# fpga.net
KiCad netlist of a schematic drawn in Altium Designer
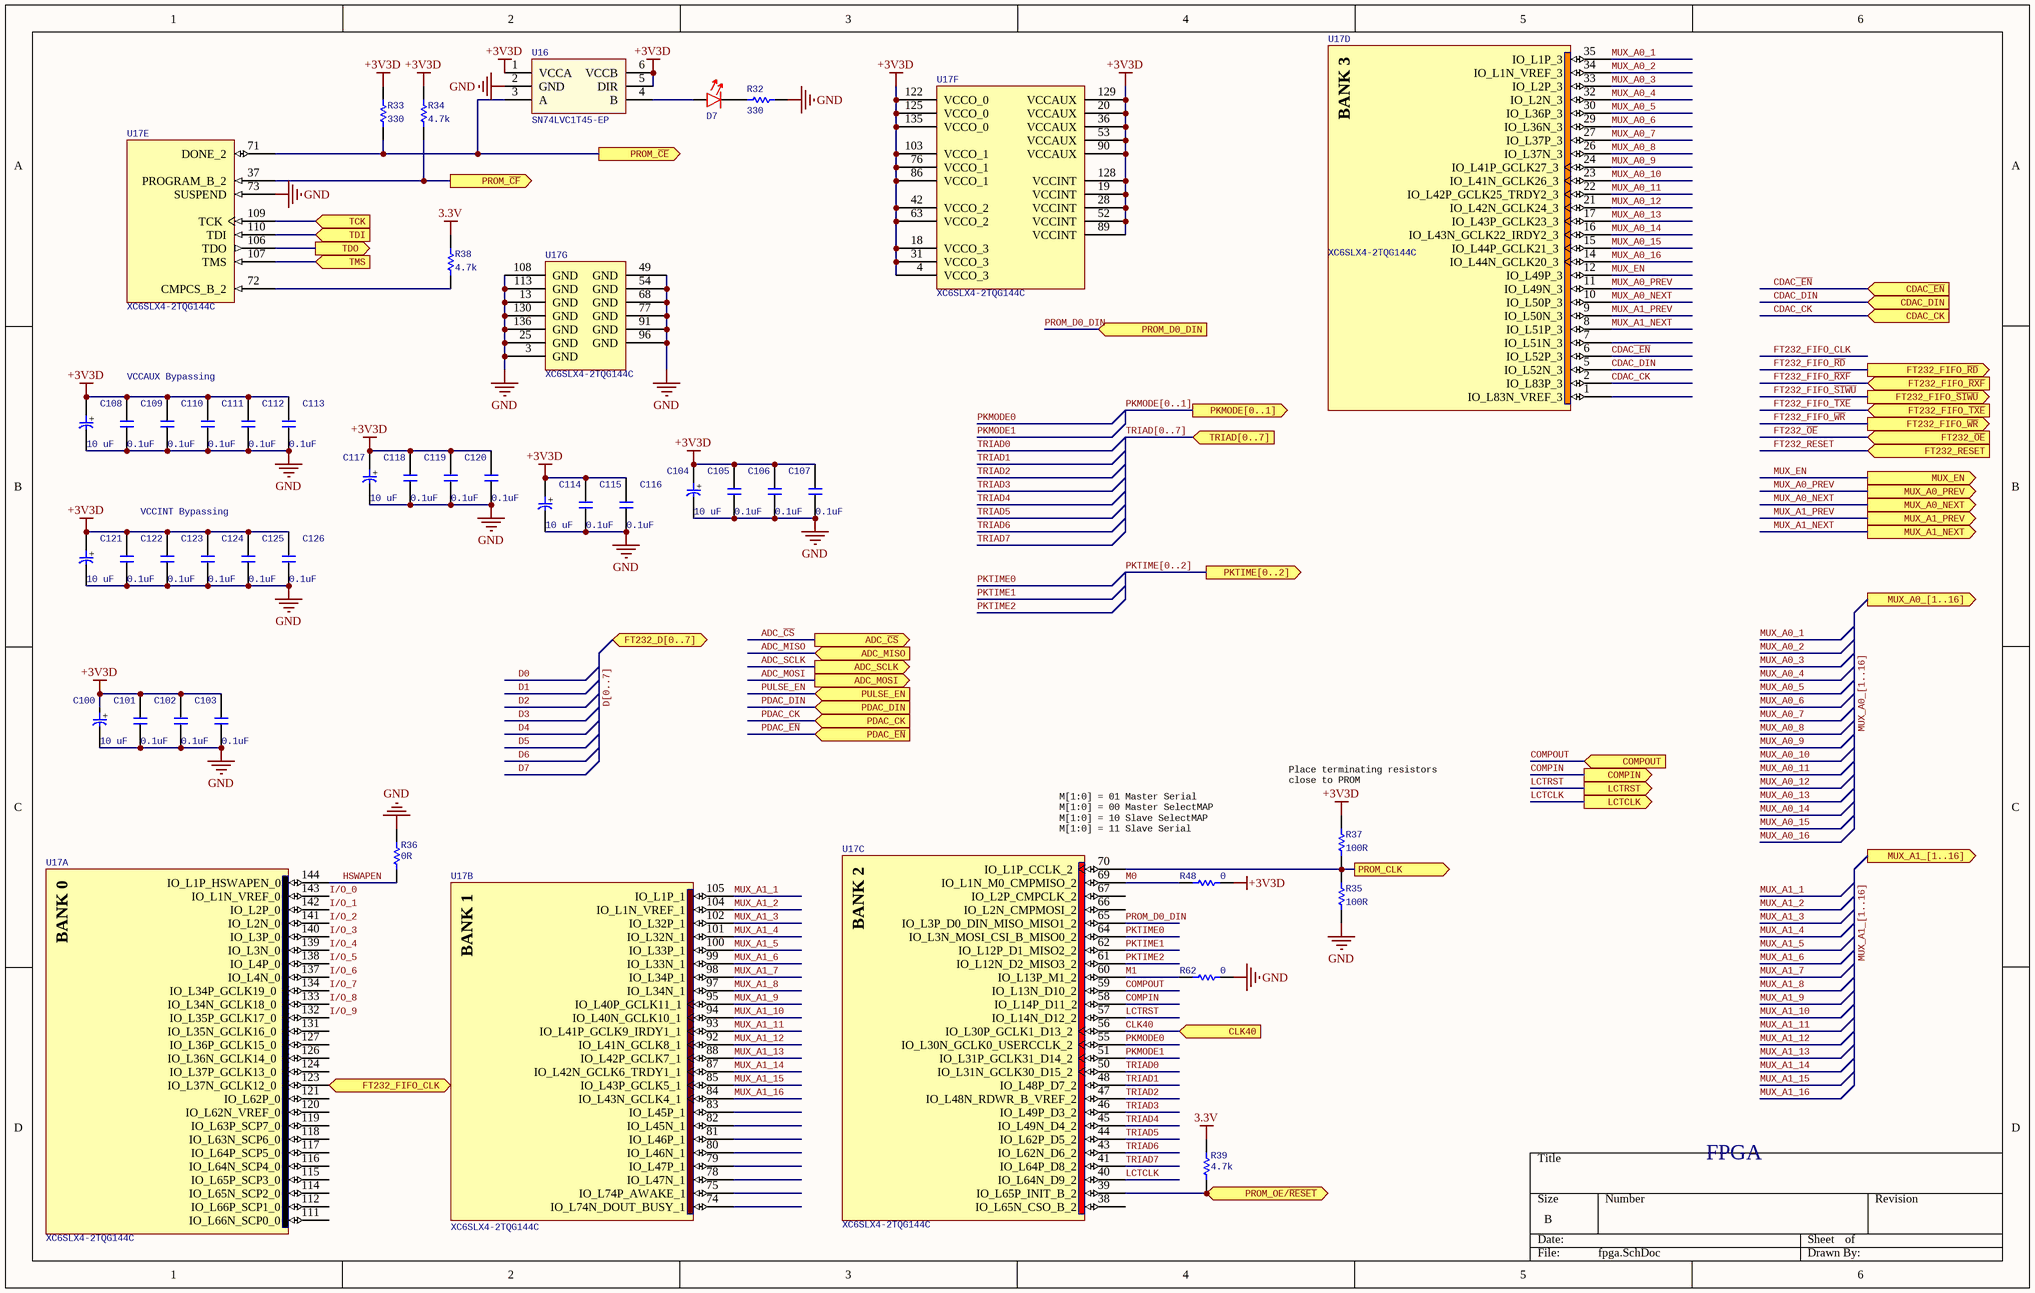
[diagram p0: fpga.SchDoc]

(export (version "E")
  (design (tool "Eeschema 10.0.6"))
  (components
    (comp (ref "C100")
      (value "10 uF")
      (footprint "KEMET 1411")
      (libsource (lib "tester_board") (part "C10uF Electro."))
    )
    (comp (ref "C101") (value "0.1uF") (footprint "0603") (libsource (lib "tester_board") (part "C0.1uF")))
    (comp (ref "C102") (value "0.1uF") (footprint "0603") (libsource (lib "tester_board") (part "C0.1uF")))
    (comp (ref "C103") (value "0.1uF") (footprint "0603") (libsource (lib "tester_board") (part "C0.1uF")))
    (comp (ref "C104")
      (value "10 uF")
      (footprint "KEMET 1411")
      (libsource (lib "tester_board") (part "C10uF Electro."))
    )
    (comp (ref "C105") (value "0.1uF") (footprint "0603") (libsource (lib "tester_board") (part "C0.1uF")))
    (comp (ref "C106") (value "0.1uF") (footprint "0603") (libsource (lib "tester_board") (part "C0.1uF")))
    (comp (ref "C107") (value "0.1uF") (footprint "0603") (libsource (lib "tester_board") (part "C0.1uF")))
    (comp (ref "C108")
      (value "10 uF")
      (footprint "KEMET 1411")
      (libsource (lib "tester_board") (part "C10uF Electro."))
    )
    (comp (ref "C109") (value "0.1uF") (footprint "0603") (libsource (lib "tester_board") (part "C0.1uF")))
    (comp (ref "C110") (value "0.1uF") (footprint "0603") (libsource (lib "tester_board") (part "C0.1uF")))
    (comp (ref "C111") (value "0.1uF") (footprint "0603") (libsource (lib "tester_board") (part "C0.1uF")))
    (comp (ref "C112") (value "0.1uF") (footprint "0603") (libsource (lib "tester_board") (part "C0.1uF")))
    (comp (ref "C113") (value "0.1uF") (footprint "0603") (libsource (lib "tester_board") (part "C0.1uF")))
    (comp (ref "C114")
      (value "10 uF")
      (footprint "KEMET 1411")
      (libsource (lib "tester_board") (part "C10uF Electro."))
    )
    (comp (ref "C115") (value "0.1uF") (footprint "0603") (libsource (lib "tester_board") (part "C0.1uF")))
    (comp (ref "C116") (value "0.1uF") (footprint "0603") (libsource (lib "tester_board") (part "C0.1uF")))
    (comp (ref "C117")
      (value "10 uF")
      (footprint "KEMET 1411")
      (libsource (lib "tester_board") (part "C10uF Electro."))
    )
    (comp (ref "C118") (value "0.1uF") (footprint "0603") (libsource (lib "tester_board") (part "C0.1uF")))
    (comp (ref "C119") (value "0.1uF") (footprint "0603") (libsource (lib "tester_board") (part "C0.1uF")))
    (comp (ref "C120") (value "0.1uF") (footprint "0603") (libsource (lib "tester_board") (part "C0.1uF")))
    (comp (ref "C121")
      (value "10 uF")
      (footprint "KEMET 1411")
      (libsource (lib "tester_board") (part "C10uF Electro."))
    )
    (comp (ref "C122") (value "0.1uF") (footprint "0603") (libsource (lib "tester_board") (part "C0.1uF")))
    (comp (ref "C123") (value "0.1uF") (footprint "0603") (libsource (lib "tester_board") (part "C0.1uF")))
    (comp (ref "C124") (value "0.1uF") (footprint "0603") (libsource (lib "tester_board") (part "C0.1uF")))
    (comp (ref "C125") (value "0.1uF") (footprint "0603") (libsource (lib "tester_board") (part "C0.1uF")))
    (comp (ref "C126") (value "0.1uF") (footprint "0603") (libsource (lib "tester_board") (part "C0.1uF")))
    (comp (ref "D7")
      (value "LED_RED")
      (fields
        (field (name "MANUFACTURER") "Lite-On Inc")
        (field (name "MANUFACTURER PART NUMBER") "LTST-C191KRKT")
      )
      (libsource (lib "tester_board") (part "LED_RED"))
    )
    (comp (ref "R32")
      (value "330")
      (footprint "0603")
      (description "R330")
      (libsource (lib "tester_board") (part "R330"))
    )
    (comp (ref "R33")
      (value "330")
      (footprint "0603")
      (description "R330")
      (libsource (lib "tester_board") (part "R330"))
    )
    (comp (ref "R34") (value "4.7k") (footprint "0603") (libsource (lib "tester_board") (part "R4K7")))
    (comp (ref "R35") (value "100R") (footprint "0603") (libsource (lib "pulse_gen") (part "R100")))
    (comp (ref "R36") (value "0R") (description "R330") (libsource (lib "piezeo_driver") (part "R0")))
    (comp (ref "R37") (value "100R") (footprint "0603") (libsource (lib "pulse_gen") (part "R100")))
    (comp (ref "R38") (value "4.7k") (footprint "0603") (libsource (lib "tester_board") (part "R4K7")))
    (comp (ref "R39") (value "4.7k") (footprint "0603") (libsource (lib "tester_board") (part "R4K7")))
    (comp (ref "R48") (value "0") (footprint "0603") (libsource (lib "tester_board") (part "R0")))
    (comp (ref "R62") (value "0") (footprint "0603") (libsource (lib "tester_board") (part "R0")))
    (comp (ref "U16")
      (value "SN74LVC1T45-EP")
      (description "SINGLE-BIT DUAL-SUPPLY BUS TRANSCEIVER")
      (libsource (lib "tester_board") (part "SN74LVC1T45-EP"))
    )
    (comp (ref "U17")
      (value "XC6SLX4-2TQG144C")
      (footprint "TQG144_L")
      (libsource (lib "tester_board") (part "FPGA-XSP6-XC6SLX9-SQ144"))
    )
  )
  (nets
    (net (code "1") (name "+3V3D") (class "Default")
      (node (ref "C100") (pin "1") (pinfunction "+_1") (pintype "passive"))
      (node (ref "C101") (pin "2") (pinfunction "2_2") (pintype "passive"))
      (node (ref "C102") (pin "2") (pinfunction "2_2") (pintype "passive"))
      (node (ref "C103") (pin "2") (pinfunction "2_2") (pintype "passive"))
      (node (ref "C104") (pin "1") (pinfunction "+_1") (pintype "passive"))
      (node (ref "C105") (pin "2") (pinfunction "2_2") (pintype "passive"))
      (node (ref "C106") (pin "2") (pinfunction "2_2") (pintype "passive"))
      (node (ref "C107") (pin "2") (pinfunction "2_2") (pintype "passive"))
      (node (ref "C108") (pin "1") (pinfunction "+_1") (pintype "passive"))
      (node (ref "C109") (pin "2") (pinfunction "2_2") (pintype "passive"))
      (node (ref "C110") (pin "2") (pinfunction "2_2") (pintype "passive"))
      (node (ref "C111") (pin "2") (pinfunction "2_2") (pintype "passive"))
      (node (ref "C112") (pin "2") (pinfunction "2_2") (pintype "passive"))
      (node (ref "C113") (pin "2") (pinfunction "2_2") (pintype "passive"))
      (node (ref "C114") (pin "1") (pinfunction "+_1") (pintype "passive"))
      (node (ref "C115") (pin "2") (pinfunction "2_2") (pintype "passive"))
      (node (ref "C116") (pin "2") (pinfunction "2_2") (pintype "passive"))
      (node (ref "C117") (pin "1") (pinfunction "+_1") (pintype "passive"))
      (node (ref "C118") (pin "2") (pinfunction "2_2") (pintype "passive"))
      (node (ref "C119") (pin "2") (pinfunction "2_2") (pintype "passive"))
      (node (ref "C120") (pin "2") (pinfunction "2_2") (pintype "passive"))
      (node (ref "C121") (pin "1") (pinfunction "+_1") (pintype "passive"))
      (node (ref "C122") (pin "2") (pinfunction "2_2") (pintype "passive"))
      (node (ref "C123") (pin "2") (pinfunction "2_2") (pintype "passive"))
      (node (ref "C124") (pin "2") (pinfunction "2_2") (pintype "passive"))
      (node (ref "C125") (pin "2") (pinfunction "2_2") (pintype "passive"))
      (node (ref "C126") (pin "2") (pinfunction "2_2") (pintype "passive"))
      (node (ref "R33") (pin "2") (pinfunction "2_2") (pintype "passive"))
      (node (ref "R34") (pin "2") (pinfunction "2_2") (pintype "passive"))
      (node (ref "R37") (pin "2") (pinfunction "2_2") (pintype "passive"))
      (node (ref "R48") (pin "2") (pinfunction "2_2") (pintype "passive"))
      (node (ref "U16") (pin "1") (pinfunction "VCCA_1") (pintype "passive"))
      (node (ref "U16") (pin "5") (pinfunction "DIR_5") (pintype "passive"))
      (node (ref "U16") (pin "6") (pinfunction "VCCB_6") (pintype "passive"))
      (node (ref "U17") (pin "103") (pinfunction "VCCO_1_103") (pintype "power_in"))
      (node (ref "U17") (pin "122") (pinfunction "VCCO_0_122") (pintype "power_in"))
      (node (ref "U17") (pin "125") (pinfunction "VCCO_0_125") (pintype "power_in"))
      (node (ref "U17") (pin "128") (pinfunction "VCCINT_128") (pintype "power_in"))
      (node (ref "U17") (pin "129") (pinfunction "VCCAUX_129") (pintype "power_in"))
      (node (ref "U17") (pin "135") (pinfunction "VCCO_0_135") (pintype "power_in"))
      (node (ref "U17") (pin "18") (pinfunction "VCCO_3_18") (pintype "power_in"))
      (node (ref "U17") (pin "19") (pinfunction "VCCINT_19") (pintype "power_in"))
      (node (ref "U17") (pin "20") (pinfunction "VCCAUX_20") (pintype "power_in"))
      (node (ref "U17") (pin "28") (pinfunction "VCCINT_28") (pintype "power_in"))
      (node (ref "U17") (pin "31") (pinfunction "VCCO_3_31") (pintype "power_in"))
      (node (ref "U17") (pin "36") (pinfunction "VCCAUX_36") (pintype "power_in"))
      (node (ref "U17") (pin "4") (pinfunction "VCCO_3_4") (pintype "power_in"))
      (node (ref "U17") (pin "42") (pinfunction "VCCO_2_42") (pintype "power_in"))
      (node (ref "U17") (pin "52") (pinfunction "VCCINT_52") (pintype "power_in"))
      (node (ref "U17") (pin "53") (pinfunction "VCCAUX_53") (pintype "power_in"))
      (node (ref "U17") (pin "63") (pinfunction "VCCO_2_63") (pintype "power_in"))
      (node (ref "U17") (pin "76") (pinfunction "VCCO_1_76") (pintype "power_in"))
      (node (ref "U17") (pin "86") (pinfunction "VCCO_1_86") (pintype "power_in"))
      (node (ref "U17") (pin "89") (pinfunction "VCCINT_89") (pintype "power_in"))
      (node (ref "U17") (pin "90") (pinfunction "VCCAUX_90") (pintype "power_in"))
    )
    (net (code "6") (name "/CDAC_CK") (class "Default")
      (node (ref "U17") (pin "2") (pinfunction "IO_L83P_3_2") (pintype "bidirectional"))
    )
    (net (code "7") (name "/CDAC_DIN") (class "Default")
      (node (ref "U17") (pin "5") (pinfunction "IO_L52N_3_5") (pintype "bidirectional"))
    )
    (net (code "8") (name "/CDAC~{_EN}") (class "Default")
      (node (ref "U17") (pin "6") (pinfunction "IO_L52P_3_6") (pintype "bidirectional"))
    )
    (net (code "9") (name "/CLK40") (class "Default")
      (node (ref "U17") (pin "56") (pinfunction "IO_L30P_GCLK1_D13_2_56") (pintype "bidirectional"))
    )
    (net (code "10") (name "/COMPIN") (class "Default")
      (node (ref "U17") (pin "58") (pinfunction "IO_L14P_D11_2_58") (pintype "bidirectional"))
    )
    (net (code "11") (name "/COMPOUT") (class "Default")
      (node (ref "U17") (pin "59") (pinfunction "IO_L13N_D10_2_59") (pintype "bidirectional"))
    )
    (net (code "20") (name "/FT232_FIFO_CLK") (class "Default")
      (node (ref "U17") (pin "123") (pinfunction "IO_L37N_GCLK12_0_123") (pintype "bidirectional"))
    )
    (net (code "28") (name "/HSWAPEN") (class "Default")
      (node (ref "R36") (pin "2") (pinfunction "2_2") (pintype "passive"))
      (node (ref "U17") (pin "144") (pinfunction "IO_L1P_HSWAPEN_0_144") (pintype "bidirectional"))
    )
    (net (code "29") (name "/I{slash}O_0") (class "Default")
      (node (ref "U17") (pin "143") (pinfunction "IO_L1N_VREF_0_143") (pintype "bidirectional"))
    )
    (net (code "30") (name "/I{slash}O_1") (class "Default")
      (node (ref "U17") (pin "142") (pinfunction "IO_L2P_0_142") (pintype "bidirectional"))
    )
    (net (code "31") (name "/I{slash}O_2") (class "Default")
      (node (ref "U17") (pin "141") (pinfunction "IO_L2N_0_141") (pintype "bidirectional"))
    )
    (net (code "32") (name "/I{slash}O_3") (class "Default")
      (node (ref "U17") (pin "140") (pinfunction "IO_L3P_0_140") (pintype "bidirectional"))
    )
    (net (code "33") (name "/I{slash}O_4") (class "Default")
      (node (ref "U17") (pin "139") (pinfunction "IO_L3N_0_139") (pintype "bidirectional"))
    )
    (net (code "34") (name "/I{slash}O_5") (class "Default")
      (node (ref "U17") (pin "138") (pinfunction "IO_L4P_0_138") (pintype "bidirectional"))
    )
    (net (code "35") (name "/I{slash}O_6") (class "Default")
      (node (ref "U17") (pin "137") (pinfunction "IO_L4N_0_137") (pintype "bidirectional"))
    )
    (net (code "36") (name "/I{slash}O_7") (class "Default")
      (node (ref "U17") (pin "134") (pinfunction "IO_L34P_GCLK19_0_134") (pintype "bidirectional"))
    )
    (net (code "37") (name "/I{slash}O_8") (class "Default")
      (node (ref "U17") (pin "133") (pinfunction "IO_L34N_GCLK18_0_133") (pintype "bidirectional"))
    )
    (net (code "38") (name "/I{slash}O_9") (class "Default")
      (node (ref "U17") (pin "132") (pinfunction "IO_L35P_GCLK17_0_132") (pintype "bidirectional"))
    )
    (net (code "39") (name "/LCTCLK") (class "Default")
      (node (ref "U17") (pin "40") (pinfunction "IO_L64N_D9_2_40") (pintype "bidirectional"))
    )
    (net (code "40") (name "/LCTRST") (class "Default")
      (node (ref "U17") (pin "57") (pinfunction "IO_L14N_D12_2_57") (pintype "bidirectional"))
    )
    (net (code "41") (name "/M0") (class "Default")
      (node (ref "R48") (pin "1") (pinfunction "1_1") (pintype "passive"))
      (node (ref "U17") (pin "69") (pinfunction "IO_L1N_M0_CMPMISO_2_69") (pintype "bidirectional"))
    )
    (net (code "42") (name "/M1") (class "Default")
      (node (ref "R62") (pin "1") (pinfunction "1_1") (pintype "passive"))
      (node (ref "U17") (pin "60") (pinfunction "IO_L13P_M1_2_60") (pintype "bidirectional"))
    )
    (net (code "43") (name "/MUX_A0_1") (class "Default")
      (node (ref "U17") (pin "35") (pinfunction "IO_L1P_3_35") (pintype "bidirectional"))
    )
    (net (code "44") (name "/MUX_A0_2") (class "Default")
      (node (ref "U17") (pin "34") (pinfunction "IO_L1N_VREF_3_34") (pintype "bidirectional"))
    )
    (net (code "45") (name "/MUX_A0_3") (class "Default")
      (node (ref "U17") (pin "33") (pinfunction "IO_L2P_3_33") (pintype "bidirectional"))
    )
    (net (code "46") (name "/MUX_A0_4") (class "Default")
      (node (ref "U17") (pin "32") (pinfunction "IO_L2N_3_32") (pintype "bidirectional"))
    )
    (net (code "47") (name "/MUX_A0_5") (class "Default")
      (node (ref "U17") (pin "30") (pinfunction "IO_L36P_3_30") (pintype "bidirectional"))
    )
    (net (code "48") (name "/MUX_A0_6") (class "Default")
      (node (ref "U17") (pin "29") (pinfunction "IO_L36N_3_29") (pintype "bidirectional"))
    )
    (net (code "49") (name "/MUX_A0_7") (class "Default")
      (node (ref "U17") (pin "27") (pinfunction "IO_L37P_3_27") (pintype "bidirectional"))
    )
    (net (code "50") (name "/MUX_A0_8") (class "Default")
      (node (ref "U17") (pin "26") (pinfunction "IO_L37N_3_26") (pintype "bidirectional"))
    )
    (net (code "51") (name "/MUX_A0_9") (class "Default")
      (node (ref "U17") (pin "24") (pinfunction "IO_L41P_GCLK27_3_24") (pintype "bidirectional"))
    )
    (net (code "52") (name "/MUX_A0_10") (class "Default")
      (node (ref "U17") (pin "23") (pinfunction "IO_L41N_GCLK26_3_23") (pintype "bidirectional"))
    )
    (net (code "53") (name "/MUX_A0_11") (class "Default")
      (node (ref "U17") (pin "22") (pinfunction "IO_L42P_GCLK25_TRDY2_3_22") (pintype "bidirectional"))
    )
    (net (code "54") (name "/MUX_A0_12") (class "Default")
      (node (ref "U17") (pin "21") (pinfunction "IO_L42N_GCLK24_3_21") (pintype "bidirectional"))
    )
    (net (code "55") (name "/MUX_A0_13") (class "Default")
      (node (ref "U17") (pin "17") (pinfunction "IO_L43P_GCLK23_3_17") (pintype "bidirectional"))
    )
    (net (code "56") (name "/MUX_A0_14") (class "Default")
      (node (ref "U17") (pin "16") (pinfunction "IO_L43N_GCLK22_IRDY2_3_16") (pintype "bidirectional"))
    )
    (net (code "57") (name "/MUX_A0_15") (class "Default")
      (node (ref "U17") (pin "15") (pinfunction "IO_L44P_GCLK21_3_15") (pintype "bidirectional"))
    )
    (net (code "58") (name "/MUX_A0_16") (class "Default")
      (node (ref "U17") (pin "14") (pinfunction "IO_L44N_GCLK20_3_14") (pintype "bidirectional"))
    )
    (net (code "59") (name "/MUX_A0_NEXT") (class "Default")
      (node (ref "U17") (pin "10") (pinfunction "IO_L50P_3_10") (pintype "bidirectional"))
    )
    (net (code "60") (name "/MUX_A0_PREV") (class "Default")
      (node (ref "U17") (pin "11") (pinfunction "IO_L49N_3_11") (pintype "bidirectional"))
    )
    (net (code "61") (name "/MUX_A1_1") (class "Default")
      (node (ref "U17") (pin "105") (pinfunction "IO_L1P_1_105") (pintype "bidirectional"))
    )
    (net (code "62") (name "/MUX_A1_2") (class "Default")
      (node (ref "U17") (pin "104") (pinfunction "IO_L1N_VREF_1_104") (pintype "bidirectional"))
    )
    (net (code "63") (name "/MUX_A1_3") (class "Default")
      (node (ref "U17") (pin "102") (pinfunction "IO_L32P_1_102") (pintype "bidirectional"))
    )
    (net (code "64") (name "/MUX_A1_4") (class "Default")
      (node (ref "U17") (pin "101") (pinfunction "IO_L32N_1_101") (pintype "bidirectional"))
    )
    (net (code "65") (name "/MUX_A1_5") (class "Default")
      (node (ref "U17") (pin "100") (pinfunction "IO_L33P_1_100") (pintype "bidirectional"))
    )
    (net (code "66") (name "/MUX_A1_6") (class "Default")
      (node (ref "U17") (pin "99") (pinfunction "IO_L33N_1_99") (pintype "bidirectional"))
    )
    (net (code "67") (name "/MUX_A1_7") (class "Default")
      (node (ref "U17") (pin "98") (pinfunction "IO_L34P_1_98") (pintype "bidirectional"))
    )
    (net (code "68") (name "/MUX_A1_8") (class "Default")
      (node (ref "U17") (pin "97") (pinfunction "IO_L34N_1_97") (pintype "bidirectional"))
    )
    (net (code "69") (name "/MUX_A1_9") (class "Default")
      (node (ref "U17") (pin "95") (pinfunction "IO_L40P_GCLK11_1_95") (pintype "bidirectional"))
    )
    (net (code "70") (name "/MUX_A1_10") (class "Default")
      (node (ref "U17") (pin "94") (pinfunction "IO_L40N_GCLK10_1_94") (pintype "bidirectional"))
    )
    (net (code "71") (name "/MUX_A1_11") (class "Default")
      (node (ref "U17") (pin "93") (pinfunction "IO_L41P_GCLK9_IRDY1_1_93") (pintype "bidirectional"))
    )
    (net (code "72") (name "/MUX_A1_12") (class "Default")
      (node (ref "U17") (pin "92") (pinfunction "IO_L41N_GCLK8_1_92") (pintype "bidirectional"))
    )
    (net (code "73") (name "/MUX_A1_13") (class "Default")
      (node (ref "U17") (pin "88") (pinfunction "IO_L42P_GCLK7_1_88") (pintype "bidirectional"))
    )
    (net (code "74") (name "/MUX_A1_14") (class "Default")
      (node (ref "U17") (pin "87") (pinfunction "IO_L42N_GCLK6_TRDY1_1_87") (pintype "bidirectional"))
    )
    (net (code "75") (name "/MUX_A1_15") (class "Default")
      (node (ref "U17") (pin "85") (pinfunction "IO_L43P_GCLK5_1_85") (pintype "bidirectional"))
    )
    (net (code "76") (name "/MUX_A1_16") (class "Default")
      (node (ref "U17") (pin "84") (pinfunction "IO_L43N_GCLK4_1_84") (pintype "bidirectional"))
    )
    (net (code "77") (name "/MUX_A1_NEXT") (class "Default")
      (node (ref "U17") (pin "8") (pinfunction "IO_L51P_3_8") (pintype "bidirectional"))
    )
    (net (code "78") (name "/MUX_A1_PREV") (class "Default")
      (node (ref "U17") (pin "9") (pinfunction "IO_L50N_3_9") (pintype "bidirectional"))
    )
    (net (code "79") (name "/MUX_EN") (class "Default")
      (node (ref "U17") (pin "12") (pinfunction "IO_L49P_3_12") (pintype "bidirectional"))
    )
    (net (code "83") (name "/PKMODE0") (class "Default")
      (node (ref "U17") (pin "55") (pinfunction "IO_L30N_GCLK0_USERCCLK_2_55") (pintype "bidirectional"))
    )
    (net (code "84") (name "/PKMODE1") (class "Default")
      (node (ref "U17") (pin "51") (pinfunction "IO_L31P_GCLK31_D14_2_51") (pintype "bidirectional"))
    )
    (net (code "85") (name "/PKTIME0") (class "Default")
      (node (ref "U17") (pin "64") (pinfunction "IO_L3N_MOSI_CSI_B_MISO0_2_64") (pintype "bidirectional"))
    )
    (net (code "86") (name "/PKTIME1") (class "Default")
      (node (ref "U17") (pin "62") (pinfunction "IO_L12P_D1_MISO2_2_62") (pintype "bidirectional"))
    )
    (net (code "87") (name "/PKTIME2") (class "Default")
      (node (ref "U17") (pin "61") (pinfunction "IO_L12N_D2_MISO3_2_61") (pintype "bidirectional"))
    )
    (net (code "88") (name "/PROM_CLK") (class "Default")
      (node (ref "R35") (pin "2") (pinfunction "2_2") (pintype "passive"))
      (node (ref "R37") (pin "1") (pinfunction "1_1") (pintype "passive"))
      (node (ref "U17") (pin "70") (pinfunction "IO_L1P_CCLK_2_70") (pintype "bidirectional"))
    )
    (net (code "89") (name "/PROM_D0_DIN") (class "Default")
      (node (ref "U17") (pin "65") (pinfunction "IO_L3P_D0_DIN_MISO_MISO1_2_65") (pintype "bidirectional"))
    )
    (net (code "90") (name "/PROM_OE{slash}~{RESET}") (class "Default")
      (node (ref "R39") (pin "1") (pinfunction "1_1") (pintype "passive"))
      (node (ref "U17") (pin "39") (pinfunction "IO_L65P_INIT_B_2_39") (pintype "bidirectional"))
    )
    (net (code "91") (name "/PROM_~{CE}") (class "Default")
      (node (ref "R33") (pin "1") (pinfunction "1_1") (pintype "passive"))
      (node (ref "U16") (pin "3") (pinfunction "A_3") (pintype "passive"))
      (node (ref "U17") (pin "71") (pinfunction "DONE_2_71") (pintype "bidirectional"))
    )
    (net (code "92") (name "/PROM_~{CF}") (class "Default")
      (node (ref "R34") (pin "1") (pinfunction "1_1") (pintype "passive"))
      (node (ref "U17") (pin "37") (pinfunction "PROGRAM_B_2_37") (pintype "input"))
    )
    (net (code "94") (name "/TCK") (class "Default")
      (node (ref "U17") (pin "109") (pinfunction "TCK_109") (pintype "input"))
    )
    (net (code "95") (name "/TDI") (class "Default")
      (node (ref "U17") (pin "110") (pinfunction "TDI_110") (pintype "input"))
    )
    (net (code "96") (name "/TDO") (class "Default")
      (node (ref "U17") (pin "106") (pinfunction "TDO_106") (pintype "output"))
    )
    (net (code "97") (name "/TMS") (class "Default")
      (node (ref "U17") (pin "107") (pinfunction "TMS_107") (pintype "input"))
    )
    (net (code "98") (name "/TRIAD0") (class "Default")
      (node (ref "U17") (pin "50") (pinfunction "IO_L31N_GCLK30_D15_2_50") (pintype "bidirectional"))
    )
    (net (code "99") (name "/TRIAD1") (class "Default")
      (node (ref "U17") (pin "48") (pinfunction "IO_L48P_D7_2_48") (pintype "bidirectional"))
    )
    (net (code "100") (name "/TRIAD2") (class "Default")
      (node (ref "U17") (pin "47") (pinfunction "IO_L48N_RDWR_B_VREF_2_47") (pintype "bidirectional"))
    )
    (net (code "101") (name "/TRIAD3") (class "Default")
      (node (ref "U17") (pin "46") (pinfunction "IO_L49P_D3_2_46") (pintype "bidirectional"))
    )
    (net (code "102") (name "/TRIAD4") (class "Default")
      (node (ref "U17") (pin "45") (pinfunction "IO_L49N_D4_2_45") (pintype "bidirectional"))
    )
    (net (code "103") (name "/TRIAD5") (class "Default")
      (node (ref "U17") (pin "44") (pinfunction "IO_L62P_D5_2_44") (pintype "bidirectional"))
    )
    (net (code "104") (name "/TRIAD6") (class "Default")
      (node (ref "U17") (pin "43") (pinfunction "IO_L62N_D6_2_43") (pintype "bidirectional"))
    )
    (net (code "105") (name "/TRIAD7") (class "Default")
      (node (ref "U17") (pin "41") (pinfunction "IO_L64P_D8_2_41") (pintype "bidirectional"))
    )
    (net (code "106") (name "3.3V") (class "Default")
      (node (ref "R38") (pin "2") (pinfunction "2_2") (pintype "passive"))
      (node (ref "R39") (pin "2") (pinfunction "2_2") (pintype "passive"))
    )
    (net (code "107") (name "GND") (class "Default")
      (node (ref "C100") (pin "2") (pinfunction "-_2") (pintype "passive"))
      (node (ref "C101") (pin "1") (pinfunction "5_1") (pintype "passive"))
      (node (ref "C102") (pin "1") (pinfunction "5_1") (pintype "passive"))
      (node (ref "C103") (pin "1") (pinfunction "5_1") (pintype "passive"))
      (node (ref "C104") (pin "2") (pinfunction "-_2") (pintype "passive"))
      (node (ref "C105") (pin "1") (pinfunction "5_1") (pintype "passive"))
      (node (ref "C106") (pin "1") (pinfunction "5_1") (pintype "passive"))
      (node (ref "C107") (pin "1") (pinfunction "5_1") (pintype "passive"))
      (node (ref "C108") (pin "2") (pinfunction "-_2") (pintype "passive"))
      (node (ref "C109") (pin "1") (pinfunction "5_1") (pintype "passive"))
      (node (ref "C110") (pin "1") (pinfunction "5_1") (pintype "passive"))
      (node (ref "C111") (pin "1") (pinfunction "5_1") (pintype "passive"))
      (node (ref "C112") (pin "1") (pinfunction "5_1") (pintype "passive"))
      (node (ref "C113") (pin "1") (pinfunction "5_1") (pintype "passive"))
      (node (ref "C114") (pin "2") (pinfunction "-_2") (pintype "passive"))
      (node (ref "C115") (pin "1") (pinfunction "5_1") (pintype "passive"))
      (node (ref "C116") (pin "1") (pinfunction "5_1") (pintype "passive"))
      (node (ref "C117") (pin "2") (pinfunction "-_2") (pintype "passive"))
      (node (ref "C118") (pin "1") (pinfunction "5_1") (pintype "passive"))
      (node (ref "C119") (pin "1") (pinfunction "5_1") (pintype "passive"))
      (node (ref "C120") (pin "1") (pinfunction "5_1") (pintype "passive"))
      (node (ref "C121") (pin "2") (pinfunction "-_2") (pintype "passive"))
      (node (ref "C122") (pin "1") (pinfunction "5_1") (pintype "passive"))
      (node (ref "C123") (pin "1") (pinfunction "5_1") (pintype "passive"))
      (node (ref "C124") (pin "1") (pinfunction "5_1") (pintype "passive"))
      (node (ref "C125") (pin "1") (pinfunction "5_1") (pintype "passive"))
      (node (ref "C126") (pin "1") (pinfunction "5_1") (pintype "passive"))
      (node (ref "R32") (pin "2") (pinfunction "2_2") (pintype "passive"))
      (node (ref "R35") (pin "1") (pinfunction "1_1") (pintype "passive"))
      (node (ref "R36") (pin "1") (pinfunction "1_1") (pintype "passive"))
      (node (ref "R62") (pin "2") (pinfunction "2_2") (pintype "passive"))
      (node (ref "U16") (pin "2") (pinfunction "GND_2") (pintype "passive"))
      (node (ref "U17") (pin "108") (pinfunction "GND_108") (pintype "power_in"))
      (node (ref "U17") (pin "113") (pinfunction "GND_113") (pintype "power_in"))
      (node (ref "U17") (pin "13") (pinfunction "GND_13") (pintype "power_in"))
      (node (ref "U17") (pin "130") (pinfunction "GND_130") (pintype "power_in"))
      (node (ref "U17") (pin "136") (pinfunction "GND_136") (pintype "power_in"))
      (node (ref "U17") (pin "25") (pinfunction "GND_25") (pintype "power_in"))
      (node (ref "U17") (pin "3") (pinfunction "GND_3") (pintype "power_in"))
      (node (ref "U17") (pin "49") (pinfunction "GND_49") (pintype "power_in"))
      (node (ref "U17") (pin "54") (pinfunction "GND_54") (pintype "power_in"))
      (node (ref "U17") (pin "68") (pinfunction "GND_68") (pintype "power_in"))
      (node (ref "U17") (pin "73") (pinfunction "SUSPEND_73") (pintype "input"))
      (node (ref "U17") (pin "77") (pinfunction "GND_77") (pintype "power_in"))
      (node (ref "U17") (pin "91") (pinfunction "GND_91") (pintype "power_in"))
      (node (ref "U17") (pin "96") (pinfunction "GND_96") (pintype "power_in"))
    )
    (net (code "108") (name "Net-(D7-Pad2)") (class "Default")
      (node (ref "D7") (pin "2") (pintype "passive"))
      (node (ref "R32") (pin "1") (pinfunction "1_1") (pintype "passive"))
    )
    (net (code "109") (name "Net-(U16-B)") (class "Default")
      (node (ref "D7") (pin "1") (pintype "passive"))
      (node (ref "U16") (pin "4") (pinfunction "B_4") (pintype "passive"))
    )
    (net (code "110") (name "Net-(U17E-CMPCS_B_2)") (class "Default")
      (node (ref "R38") (pin "1") (pinfunction "1_1") (pintype "passive"))
      (node (ref "U17") (pin "72") (pinfunction "CMPCS_B_2_72") (pintype "input"))
    )
    (net (code "111") (name "unconnected-(U17A-IO_L35N_GCLK16_0-Pad131)") (class "Default")
      (node (ref "U17") (pin "131") (pinfunction "IO_L35N_GCLK16_0_131") (pintype "bidirectional"))
    )
    (net (code "112") (name "unconnected-(U17A-IO_L36N_GCLK14_0-Pad126)") (class "Default")
      (node (ref "U17") (pin "126") (pinfunction "IO_L36N_GCLK14_0_126") (pintype "bidirectional"))
    )
    (net (code "113") (name "unconnected-(U17A-IO_L36P_GCLK15_0-Pad127)") (class "Default")
      (node (ref "U17") (pin "127") (pinfunction "IO_L36P_GCLK15_0_127") (pintype "bidirectional"))
    )
    (net (code "114") (name "unconnected-(U17A-IO_L37P_GCLK13_0-Pad124)") (class "Default")
      (node (ref "U17") (pin "124") (pinfunction "IO_L37P_GCLK13_0_124") (pintype "bidirectional"))
    )
    (net (code "115") (name "unconnected-(U17A-IO_L62N_VREF_0-Pad120)") (class "Default")
      (node (ref "U17") (pin "120") (pinfunction "IO_L62N_VREF_0_120") (pintype "bidirectional"))
    )
    (net (code "116") (name "unconnected-(U17A-IO_L62P_0-Pad121)") (class "Default")
      (node (ref "U17") (pin "121") (pinfunction "IO_L62P_0_121") (pintype "bidirectional"))
    )
    (net (code "117") (name "unconnected-(U17A-IO_L63N_SCP6_0-Pad118)") (class "Default")
      (node (ref "U17") (pin "118") (pinfunction "IO_L63N_SCP6_0_118") (pintype "bidirectional"))
    )
    (net (code "118") (name "unconnected-(U17A-IO_L63P_SCP7_0-Pad119)") (class "Default")
      (node (ref "U17") (pin "119") (pinfunction "IO_L63P_SCP7_0_119") (pintype "bidirectional"))
    )
    (net (code "119") (name "unconnected-(U17A-IO_L64N_SCP4_0-Pad116)") (class "Default")
      (node (ref "U17") (pin "116") (pinfunction "IO_L64N_SCP4_0_116") (pintype "bidirectional"))
    )
    (net (code "120") (name "unconnected-(U17A-IO_L64P_SCP5_0-Pad117)") (class "Default")
      (node (ref "U17") (pin "117") (pinfunction "IO_L64P_SCP5_0_117") (pintype "bidirectional"))
    )
    (net (code "121") (name "unconnected-(U17A-IO_L65N_SCP2_0-Pad114)") (class "Default")
      (node (ref "U17") (pin "114") (pinfunction "IO_L65N_SCP2_0_114") (pintype "bidirectional"))
    )
    (net (code "122") (name "unconnected-(U17A-IO_L65P_SCP3_0-Pad115)") (class "Default")
      (node (ref "U17") (pin "115") (pinfunction "IO_L65P_SCP3_0_115") (pintype "bidirectional"))
    )
    (net (code "123") (name "unconnected-(U17A-IO_L66N_SCP0_0-Pad111)") (class "Default")
      (node (ref "U17") (pin "111") (pinfunction "IO_L66N_SCP0_0_111") (pintype "bidirectional"))
    )
    (net (code "124") (name "unconnected-(U17A-IO_L66P_SCP1_0-Pad112)") (class "Default")
      (node (ref "U17") (pin "112") (pinfunction "IO_L66P_SCP1_0_112") (pintype "bidirectional"))
    )
    (net (code "125") (name "unconnected-(U17B-IO_L45N_1-Pad82)") (class "Default")
      (node (ref "U17") (pin "82") (pinfunction "IO_L45N_1_82") (pintype "bidirectional"))
    )
    (net (code "126") (name "unconnected-(U17B-IO_L45P_1-Pad83)") (class "Default")
      (node (ref "U17") (pin "83") (pinfunction "IO_L45P_1_83") (pintype "bidirectional"))
    )
    (net (code "127") (name "unconnected-(U17B-IO_L46N_1-Pad80)") (class "Default")
      (node (ref "U17") (pin "80") (pinfunction "IO_L46N_1_80") (pintype "bidirectional"))
    )
    (net (code "128") (name "unconnected-(U17B-IO_L46P_1-Pad81)") (class "Default")
      (node (ref "U17") (pin "81") (pinfunction "IO_L46P_1_81") (pintype "bidirectional"))
    )
    (net (code "129") (name "unconnected-(U17B-IO_L47N_1-Pad78)") (class "Default")
      (node (ref "U17") (pin "78") (pinfunction "IO_L47N_1_78") (pintype "bidirectional"))
    )
    (net (code "130") (name "unconnected-(U17B-IO_L47P_1-Pad79)") (class "Default")
      (node (ref "U17") (pin "79") (pinfunction "IO_L47P_1_79") (pintype "bidirectional"))
    )
    (net (code "131") (name "unconnected-(U17B-IO_L74N_DOUT_BUSY_1-Pad74)") (class "Default")
      (node (ref "U17") (pin "74") (pinfunction "IO_L74N_DOUT_BUSY_1_74") (pintype "bidirectional"))
    )
    (net (code "132") (name "unconnected-(U17B-IO_L74P_AWAKE_1-Pad75)") (class "Default")
      (node (ref "U17") (pin "75") (pinfunction "IO_L74P_AWAKE_1_75") (pintype "bidirectional"))
    )
    (net (code "133") (name "unconnected-(U17C-IO_L2N_CMPMOSI_2-Pad66)") (class "Default")
      (node (ref "U17") (pin "66") (pinfunction "IO_L2N_CMPMOSI_2_66") (pintype "bidirectional"))
    )
    (net (code "134") (name "unconnected-(U17C-IO_L2P_CMPCLK_2-Pad67)") (class "Default")
      (node (ref "U17") (pin "67") (pinfunction "IO_L2P_CMPCLK_2_67") (pintype "bidirectional"))
    )
    (net (code "135") (name "unconnected-(U17C-IO_L65N_CSO_B_2-Pad38)") (class "Default")
      (node (ref "U17") (pin "38") (pinfunction "IO_L65N_CSO_B_2_38") (pintype "bidirectional"))
    )
    (net (code "136") (name "unconnected-(U17D-IO_L51N_3-Pad7)") (class "Default")
      (node (ref "U17") (pin "7") (pinfunction "IO_L51N_3_7") (pintype "bidirectional"))
    )
    (net (code "137") (name "unconnected-(U17D-IO_L83N_VREF_3-Pad1)") (class "Default")
      (node (ref "U17") (pin "1") (pinfunction "IO_L83N_VREF_3_1") (pintype "bidirectional"))
    )
  )
)
